# Connectors.net
KiCad netlist of a schematic drawn in Altium Designer
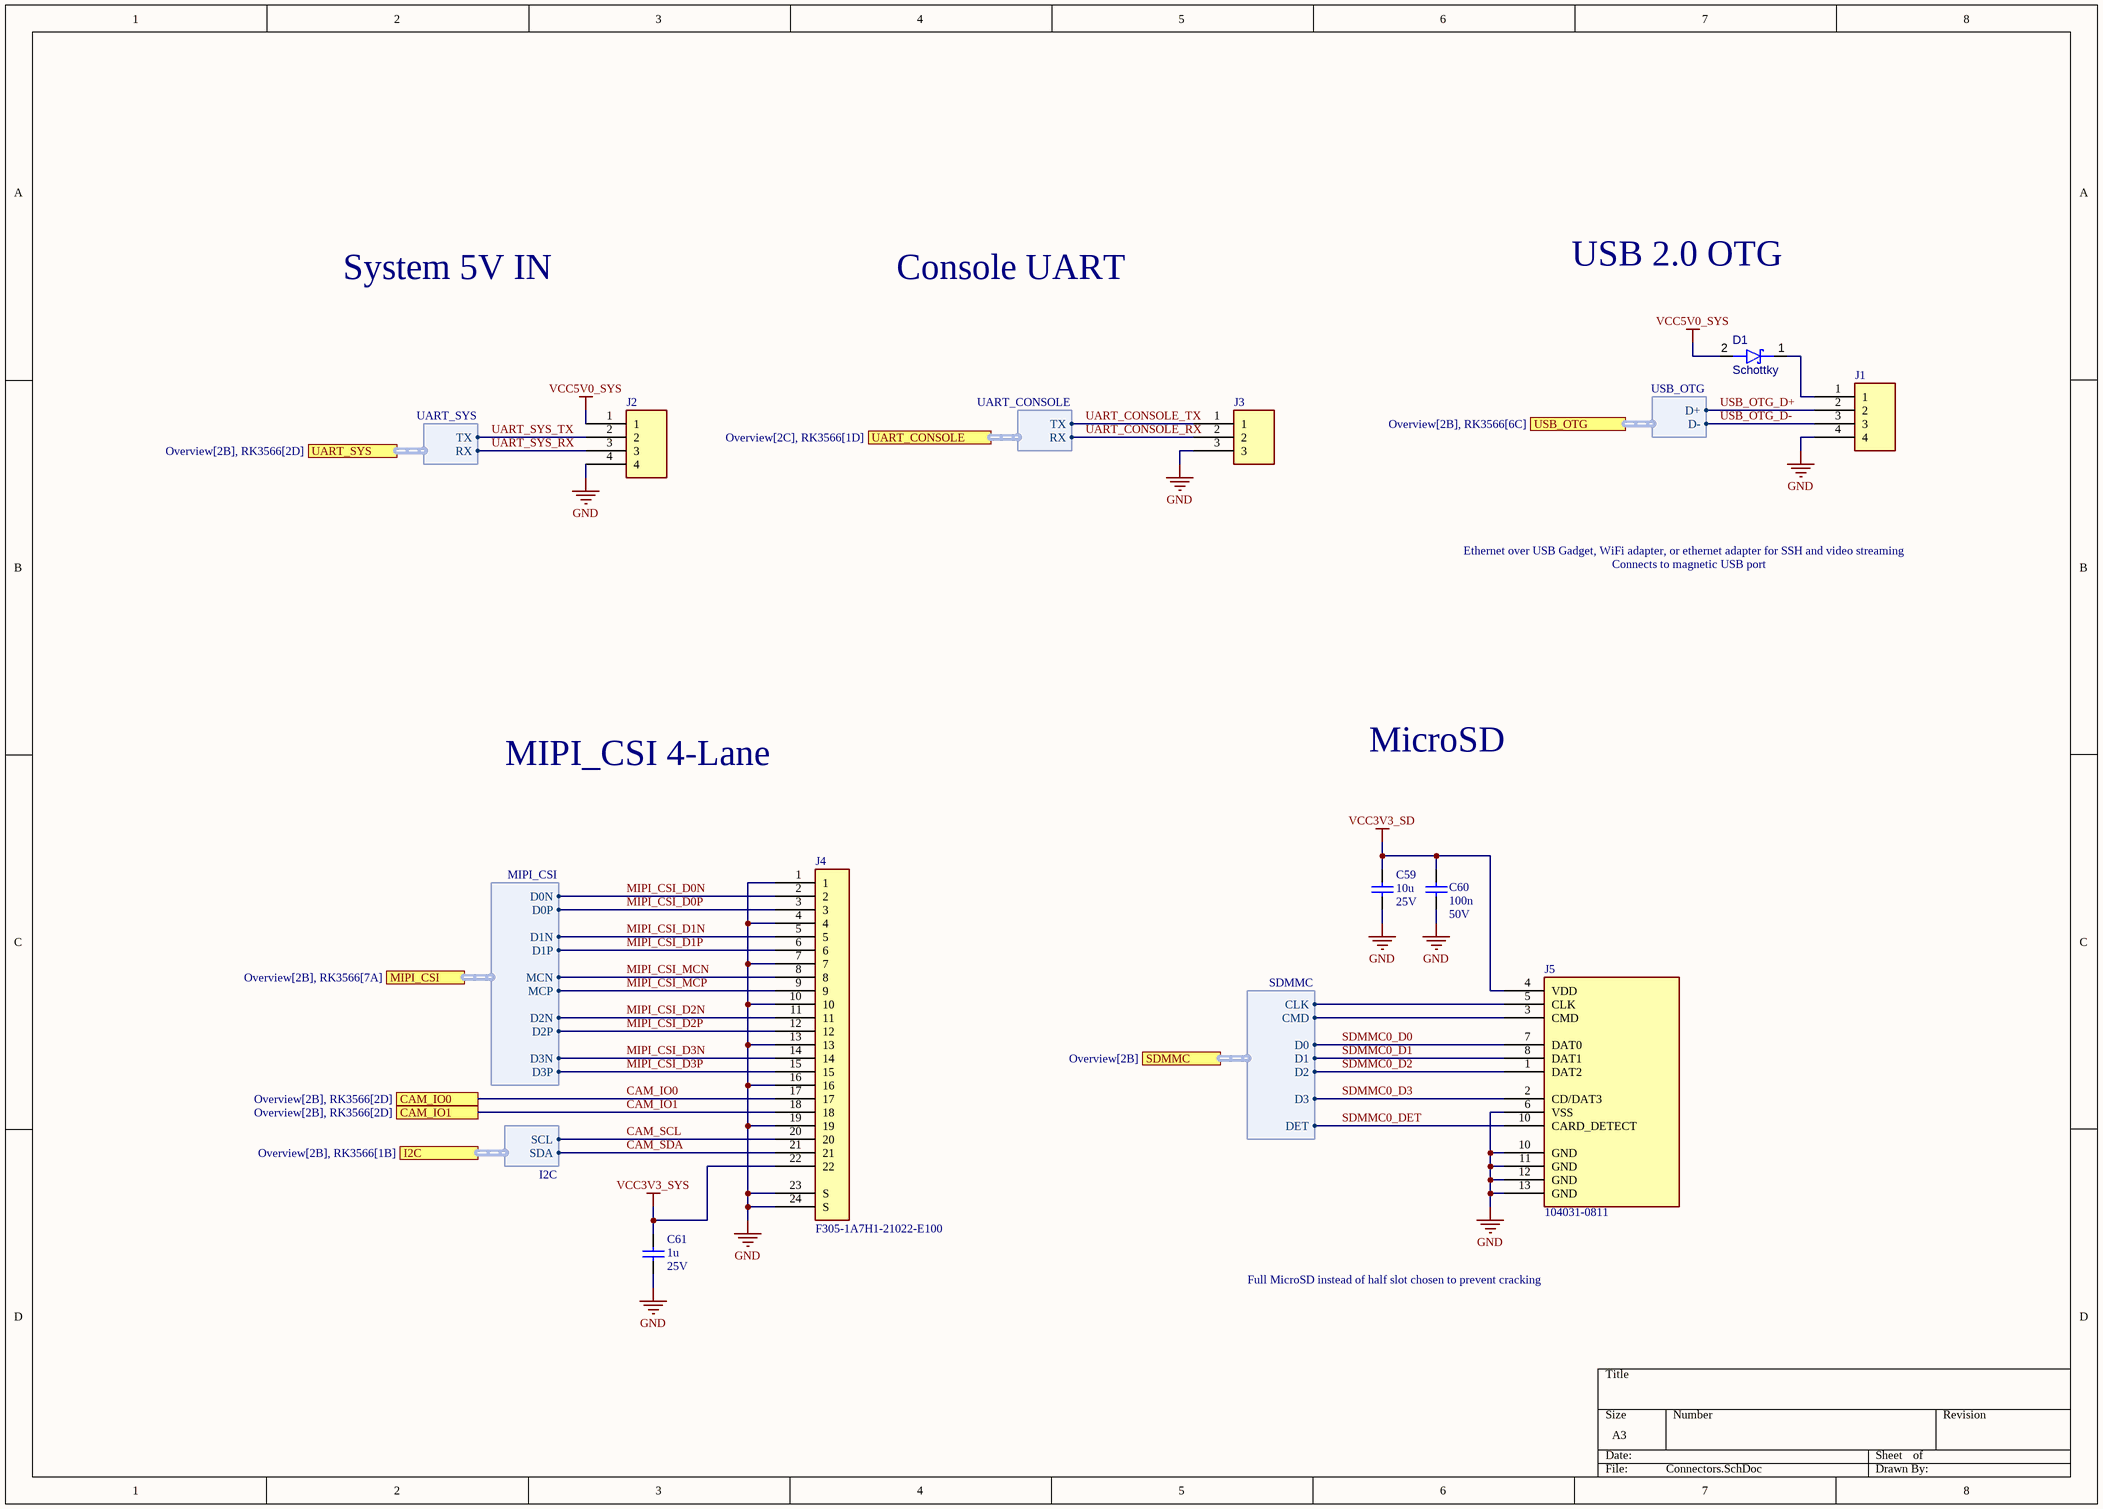
[diagram p0: Connectors.SchDoc]

(export (version "E")
  (design (tool "Eeschema 10.0.6"))
  (components
    (comp (ref "C59")
      (value "10u")
      (description "CAP 10U 25V X5R 0603")
      (fields (field (name "VOLTAGE") "25V") (field (name "Comment") "GRM188R61E106MA73D"))
      (libsource (lib "PersonalAltiumLibrary") (part "GRM188R61E106MA73D"))
    )
    (comp (ref "C60")
      (value "100n")
      (footprint "GRM155R71H104KE14D")
      (description "CAP 100N 50V X7R 0402")
      (fields (field (name "VOLTAGE") "50V") (field (name "Comment") "GRM155R71H104KE14D"))
      (libsource (lib "PersonalAltiumLibrary") (part "GRM155R71H104KE14D"))
    )
    (comp (ref "C61")
      (value "1u")
      (footprint "GRM155R61E105KA12D")
      (description "CAP 1U 25V X5R 0402")
      (fields (field (name "VOLTAGE") "25V") (field (name "Comment") "GRM155R61E105KA12D"))
      (libsource (lib "PersonalAltiumLibrary") (part "GRM155R61E105KA12D"))
    )
    (comp (ref "D1")
      (value "Schottky")
      (footprint "MicroSMP (DO-219AD)")
      (description "Diode")
      (libsource (lib "PersonalAltiumLibrary") (part "Schottky"))
    )
    (comp (ref "J1")
      (value "SM04B-SRSS-TB")
      (footprint "SM04B-SRSS-TB")
      (description "JST-SH 4P")
      (libsource (lib "PersonalAltiumLibrary") (part "SM04B-SRSS-TB"))
    )
    (comp (ref "J2")
      (value "SM04B-SRSS-TB")
      (footprint "SM04B-SRSS-TB")
      (description "JST-SH 4P")
      (libsource (lib "PersonalAltiumLibrary") (part "SM04B-SRSS-TB"))
    )
    (comp (ref "J3")
      (value "SM03B-SRSS-TB")
      (footprint "SM03B-SRSS-TB")
      (description "JST-SH 3P")
      (libsource (lib "PersonalAltiumLibrary") (part "SM03B-SRSS-TB"))
    )
    (comp (ref "J4")
      (value "F305-1A7H1-21022-E100")
      (footprint "F305-1A7H1-21022-E100")
      (description "FPC")
      (libsource (lib "PersonalAltiumLibrary") (part "F305-1A7H1-21022-E100"))
    )
    (comp (ref "J5")
      (value "104031-0811")
      (footprint "104031-0811")
      (description "Micro SD")
      (libsource (lib "PersonalAltiumLibrary") (part "104031-0811"))
    )
  )
  (nets
    (net (code "7") (name "/CAM_IO0") (class "Default")
      (node (ref "J4") (pin "17") (pinfunction "17_17") (pintype "passive"))
    )
    (net (code "8") (name "/CAM_IO1") (class "Default")
      (node (ref "J4") (pin "18") (pinfunction "18_18") (pintype "passive"))
    )
    (net (code "9") (name "/CAM_SCL") (class "Default")
      (node (ref "J4") (pin "20") (pinfunction "20_20") (pintype "passive"))
    )
    (net (code "10") (name "/CAM_SDA") (class "Default")
      (node (ref "J4") (pin "21") (pinfunction "21_21") (pintype "passive"))
    )
    (net (code "11") (name "/CLK") (class "Default")
      (node (ref "J5") (pin "5") (pinfunction "CLK_5") (pintype "passive"))
    )
    (net (code "12") (name "/CMD") (class "Default")
      (node (ref "J5") (pin "3") (pinfunction "CMD_3") (pintype "passive"))
    )
    (net (code "13") (name "/MIPI_CSI_D0N") (class "Default")
      (node (ref "J4") (pin "2") (pinfunction "2_2") (pintype "passive"))
    )
    (net (code "14") (name "/MIPI_CSI_D0P") (class "Default")
      (node (ref "J4") (pin "3") (pinfunction "3_3") (pintype "passive"))
    )
    (net (code "15") (name "/MIPI_CSI_D1N") (class "Default")
      (node (ref "J4") (pin "5") (pinfunction "5_5") (pintype "passive"))
    )
    (net (code "16") (name "/MIPI_CSI_D1P") (class "Default")
      (node (ref "J4") (pin "6") (pinfunction "6_6") (pintype "passive"))
    )
    (net (code "17") (name "/MIPI_CSI_D2N") (class "Default")
      (node (ref "J4") (pin "11") (pinfunction "11_11") (pintype "passive"))
    )
    (net (code "18") (name "/MIPI_CSI_D2P") (class "Default")
      (node (ref "J4") (pin "12") (pinfunction "12_12") (pintype "passive"))
    )
    (net (code "19") (name "/MIPI_CSI_D3N") (class "Default")
      (node (ref "J4") (pin "14") (pinfunction "14_14") (pintype "passive"))
    )
    (net (code "20") (name "/MIPI_CSI_D3P") (class "Default")
      (node (ref "J4") (pin "15") (pinfunction "15_15") (pintype "passive"))
    )
    (net (code "21") (name "/MIPI_CSI_MCN") (class "Default")
      (node (ref "J4") (pin "8") (pinfunction "8_8") (pintype "passive"))
    )
    (net (code "22") (name "/MIPI_CSI_MCP") (class "Default")
      (node (ref "J4") (pin "9") (pinfunction "9_9") (pintype "passive"))
    )
    (net (code "23") (name "/SDMMC0_D0") (class "Default")
      (node (ref "J5") (pin "7") (pinfunction "DAT0_7") (pintype "passive"))
    )
    (net (code "24") (name "/SDMMC0_D1") (class "Default")
      (node (ref "J5") (pin "8") (pinfunction "DAT1_8") (pintype "passive"))
    )
    (net (code "25") (name "/SDMMC0_D2") (class "Default")
      (node (ref "J5") (pin "1") (pinfunction "DAT2_1") (pintype "passive"))
    )
    (net (code "26") (name "/SDMMC0_D3") (class "Default")
      (node (ref "J5") (pin "2") (pinfunction "CD/DAT3_2") (pintype "passive"))
    )
    (net (code "27") (name "/SDMMC0_DET") (class "Default")
      (node (ref "J5") (pin "10") (pinfunction "CARD_DETECT_10") (pintype "passive"))
    )
    (net (code "28") (name "/UART_CONSOLE_RX") (class "Default")
      (node (ref "J3") (pin "2") (pinfunction "2_2") (pintype "passive"))
    )
    (net (code "29") (name "/UART_CONSOLE_TX") (class "Default")
      (node (ref "J3") (pin "1") (pinfunction "1_1") (pintype "passive"))
    )
    (net (code "30") (name "/UART_SYS_RX") (class "Default")
      (node (ref "J2") (pin "3") (pinfunction "3_3") (pintype "passive"))
    )
    (net (code "31") (name "/UART_SYS_TX") (class "Default")
      (node (ref "J2") (pin "2") (pinfunction "2_2") (pintype "passive"))
    )
    (net (code "32") (name "/USB_OTG_D+") (class "Default")
      (node (ref "J1") (pin "2") (pinfunction "2_2") (pintype "passive"))
    )
    (net (code "33") (name "/USB_OTG_D-") (class "Default")
      (node (ref "J1") (pin "3") (pinfunction "3_3") (pintype "passive"))
    )
    (net (code "40") (name "GND") (class "Default")
      (node (ref "C59") (pin "2") (pinfunction "2_2") (pintype "passive"))
      (node (ref "C60") (pin "2") (pinfunction "2_2") (pintype "passive"))
      (node (ref "C61") (pin "2") (pinfunction "2_2") (pintype "passive"))
      (node (ref "J1") (pin "4") (pinfunction "4_4") (pintype "passive"))
      (node (ref "J2") (pin "4") (pinfunction "4_4") (pintype "passive"))
      (node (ref "J3") (pin "3") (pinfunction "3_3") (pintype "passive"))
      (node (ref "J4") (pin "1") (pinfunction "1_1") (pintype "passive"))
      (node (ref "J4") (pin "10") (pinfunction "10_10") (pintype "passive"))
      (node (ref "J4") (pin "13") (pinfunction "13_13") (pintype "passive"))
      (node (ref "J4") (pin "16") (pinfunction "16_16") (pintype "passive"))
      (node (ref "J4") (pin "19") (pinfunction "19_19") (pintype "passive"))
      (node (ref "J4") (pin "23") (pinfunction "S_23") (pintype "passive"))
      (node (ref "J4") (pin "24") (pinfunction "S_24") (pintype "passive"))
      (node (ref "J4") (pin "4") (pinfunction "4_4") (pintype "passive"))
      (node (ref "J4") (pin "7") (pinfunction "7_7") (pintype "passive"))
      (node (ref "J5") (pin "10") (pinfunction "GND_10") (pintype "passive"))
      (node (ref "J5") (pin "11") (pinfunction "GND_11") (pintype "passive"))
      (node (ref "J5") (pin "12") (pinfunction "GND_12") (pintype "passive"))
      (node (ref "J5") (pin "13") (pinfunction "GND_13") (pintype "passive"))
      (node (ref "J5") (pin "6") (pinfunction "VSS_6") (pintype "passive"))
    )
    (net (code "41") (name "Net-(D1-K)") (class "Default")
      (node (ref "D1") (pin "1") (pinfunction "K_1") (pintype "passive"))
      (node (ref "J1") (pin "1") (pinfunction "1_1") (pintype "passive"))
    )
    (net (code "42") (name "VCC3V3_SD") (class "Default")
      (node (ref "C59") (pin "1") (pinfunction "1_1") (pintype "passive"))
      (node (ref "C60") (pin "1") (pinfunction "1_1") (pintype "passive"))
      (node (ref "J5") (pin "4") (pinfunction "VDD_4") (pintype "passive"))
    )
    (net (code "43") (name "VCC3V3_SYS") (class "Default")
      (node (ref "C61") (pin "1") (pinfunction "1_1") (pintype "passive"))
      (node (ref "J4") (pin "22") (pinfunction "22_22") (pintype "passive"))
    )
    (net (code "44") (name "VCC5V0_SYS") (class "Default")
      (node (ref "D1") (pin "2") (pinfunction "A_2") (pintype "passive"))
      (node (ref "J2") (pin "1") (pinfunction "1_1") (pintype "passive"))
    )
  )
)
